# QFN-20_0_4mm.net
KiCad netlist of a schematic drawn in EAGLE
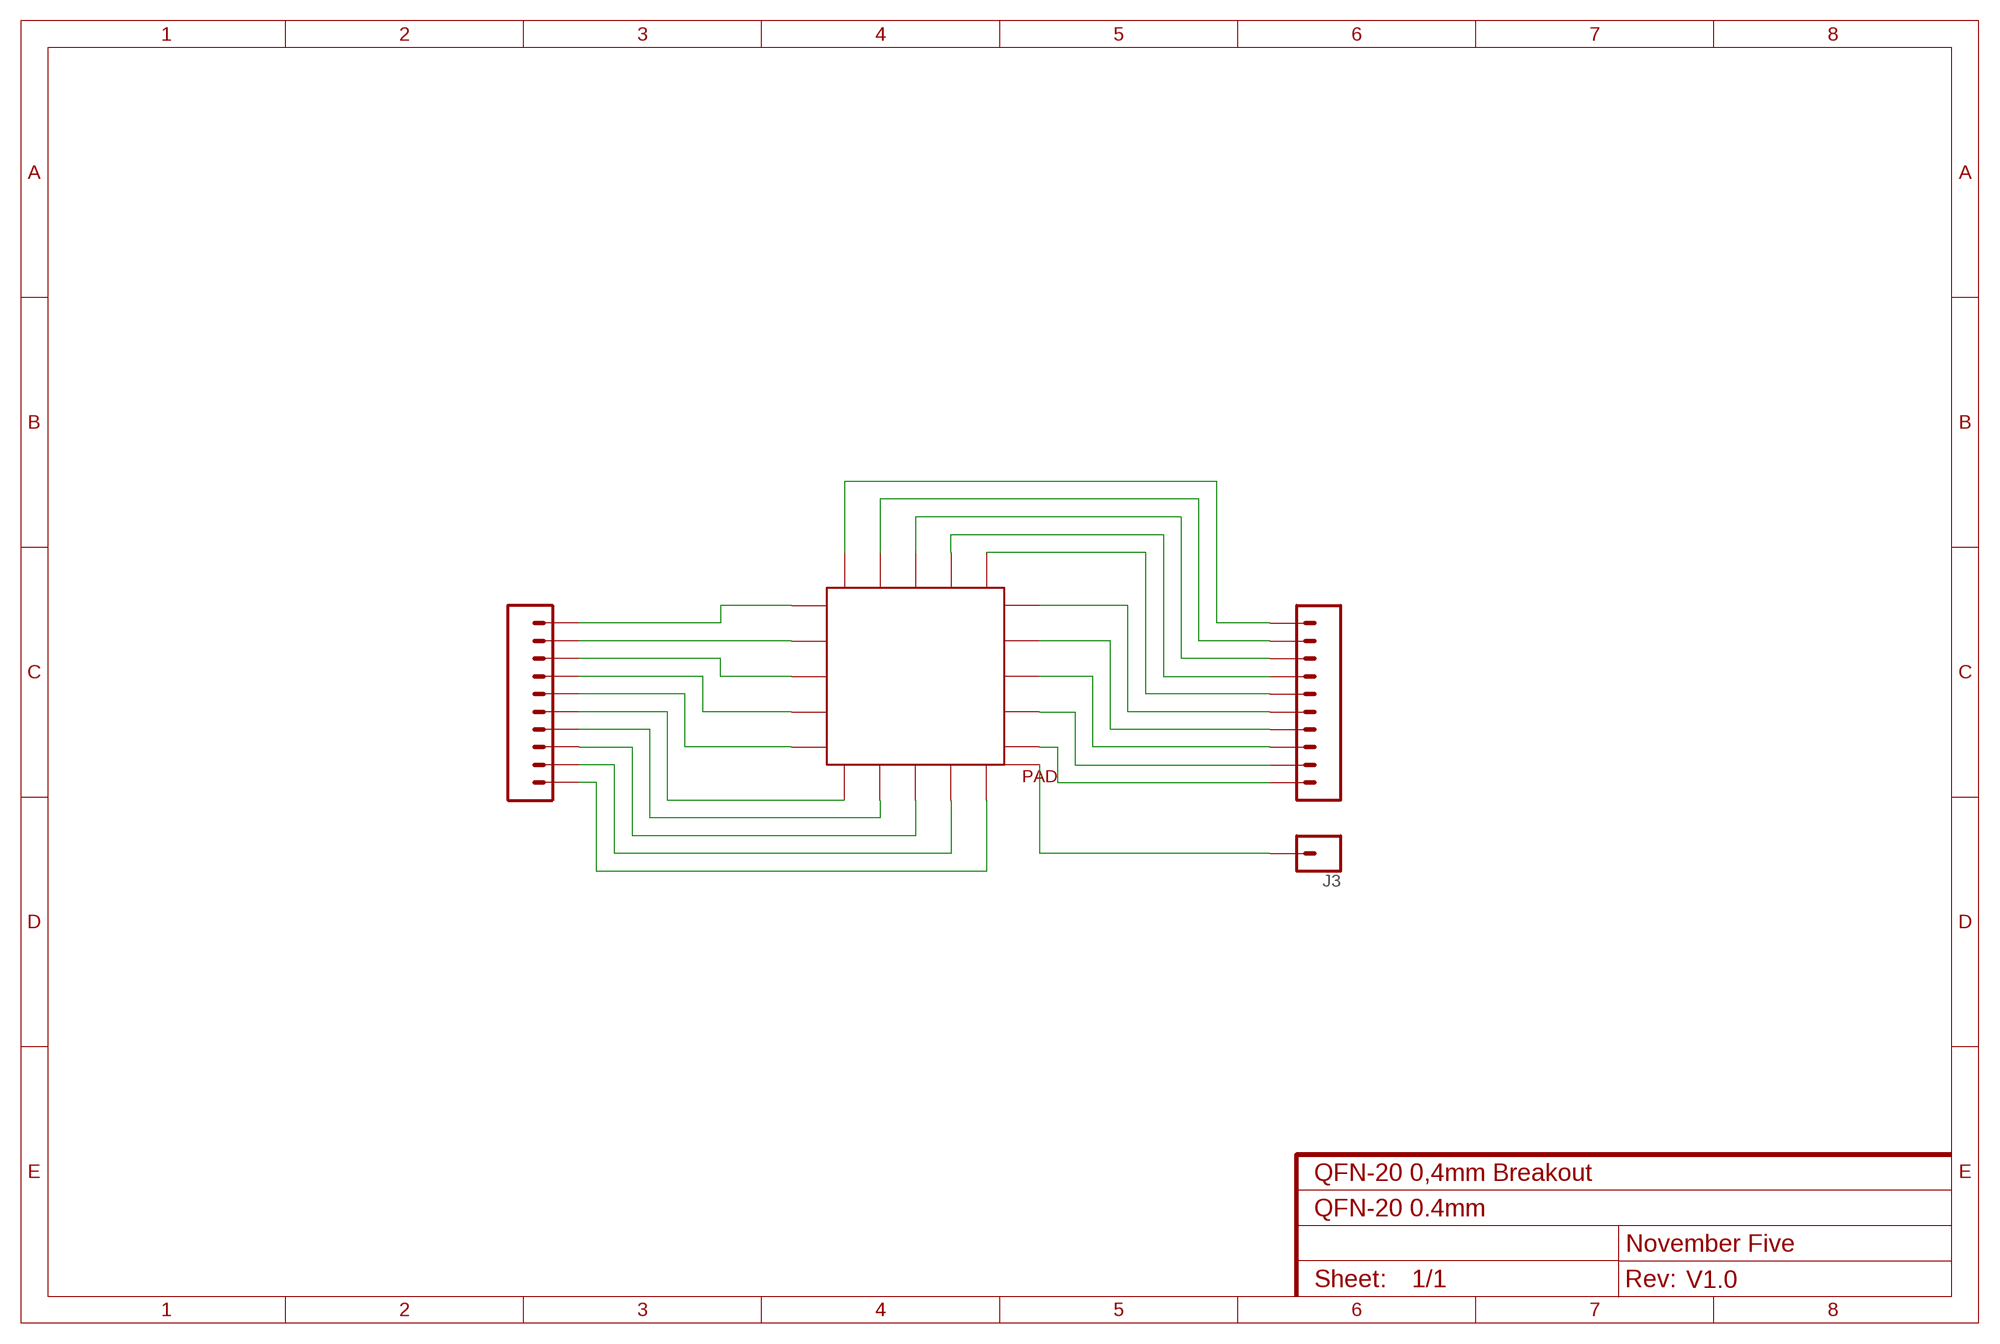
[diagram p0: schematic, sheet 1]

(export (version "E")
  (design (tool "Eeschema 10.0.6"))
  (components
    (comp (ref "GND")
      (value "QFN-20_0,4MM")
      (footprint "eagle-import:QFN20_0,4MM")
      (libsource (lib "eagle-import") (part "QFN-20_0,4MM"))
    )
    (comp (ref "J1")
      (value "CONN_10\"")
      (footprint "eagle-import:1X10")
      (libsource (lib "eagle-import") (part "CONN_10{dblquote}"))
    )
    (comp (ref "J2")
      (value "CONN_10\"")
      (footprint "eagle-import:1X10")
      (libsource (lib "eagle-import") (part "CONN_10{dblquote}"))
    )
    (comp (ref "J3")
      (value "CONN_01")
      (footprint "eagle-import:1X01")
      (libsource (lib "eagle-import") (part "CONN_01"))
    )
  )
  (nets
    (net (code "1") (name "Net-(GND-PAD)") (class "Default")
      (node (ref "GND") (pin "0") (pinfunction "PAD_0") (pintype "power_in"))
      (node (ref "J3") (pin "1") (pinfunction "1_1") (pintype "passive"))
    )
    (net (code "2") (name "Net-(GND-PIN1)") (class "Default")
      (node (ref "GND") (pin "1") (pinfunction "PIN1_1") (pintype "bidirectional"))
      (node (ref "J1") (pin "1") (pinfunction "1_1") (pintype "passive"))
    )
    (net (code "3") (name "Net-(GND-PIN2)") (class "Default")
      (node (ref "GND") (pin "2") (pinfunction "PIN2_2") (pintype "bidirectional"))
      (node (ref "J1") (pin "2") (pinfunction "2_2") (pintype "passive"))
    )
    (net (code "4") (name "Net-(GND-PIN3)") (class "Default")
      (node (ref "GND") (pin "3") (pinfunction "PIN3_3") (pintype "bidirectional"))
      (node (ref "J1") (pin "3") (pinfunction "3_3") (pintype "passive"))
    )
    (net (code "5") (name "Net-(GND-PIN4)") (class "Default")
      (node (ref "GND") (pin "4") (pinfunction "PIN4_4") (pintype "bidirectional"))
      (node (ref "J1") (pin "4") (pinfunction "4_4") (pintype "passive"))
    )
    (net (code "6") (name "Net-(GND-PIN5)") (class "Default")
      (node (ref "GND") (pin "5") (pinfunction "PIN5_5") (pintype "bidirectional"))
      (node (ref "J1") (pin "5") (pinfunction "5_5") (pintype "passive"))
    )
    (net (code "7") (name "Net-(GND-PIN6)") (class "Default")
      (node (ref "GND") (pin "6") (pinfunction "PIN6_6") (pintype "bidirectional"))
      (node (ref "J1") (pin "6") (pinfunction "6_6") (pintype "passive"))
    )
    (net (code "8") (name "Net-(GND-PIN7)") (class "Default")
      (node (ref "GND") (pin "7") (pinfunction "PIN7_7") (pintype "bidirectional"))
      (node (ref "J1") (pin "7") (pinfunction "7_7") (pintype "passive"))
    )
    (net (code "9") (name "Net-(GND-PIN8)") (class "Default")
      (node (ref "GND") (pin "8") (pinfunction "PIN8_8") (pintype "bidirectional"))
      (node (ref "J1") (pin "8") (pinfunction "8_8") (pintype "passive"))
    )
    (net (code "10") (name "Net-(GND-PIN9)") (class "Default")
      (node (ref "GND") (pin "9") (pinfunction "PIN9_9") (pintype "bidirectional"))
      (node (ref "J1") (pin "9") (pinfunction "9_9") (pintype "passive"))
    )
    (net (code "11") (name "Net-(GND-PIN10)") (class "Default")
      (node (ref "GND") (pin "10") (pinfunction "PIN10_10") (pintype "bidirectional"))
      (node (ref "J1") (pin "10") (pinfunction "10_10") (pintype "passive"))
    )
    (net (code "12") (name "Net-(GND-PIN11)") (class "Default")
      (node (ref "GND") (pin "11") (pinfunction "PIN11_11") (pintype "bidirectional"))
      (node (ref "J2") (pin "10") (pinfunction "10_10") (pintype "passive"))
    )
    (net (code "13") (name "Net-(GND-PIN12)") (class "Default")
      (node (ref "GND") (pin "12") (pinfunction "PIN12_12") (pintype "bidirectional"))
      (node (ref "J2") (pin "9") (pinfunction "9_9") (pintype "passive"))
    )
    (net (code "14") (name "Net-(GND-PIN13)") (class "Default")
      (node (ref "GND") (pin "13") (pinfunction "PIN13_13") (pintype "bidirectional"))
      (node (ref "J2") (pin "8") (pinfunction "8_8") (pintype "passive"))
    )
    (net (code "15") (name "Net-(GND-PIN14)") (class "Default")
      (node (ref "GND") (pin "14") (pinfunction "PIN14_14") (pintype "bidirectional"))
      (node (ref "J2") (pin "7") (pinfunction "7_7") (pintype "passive"))
    )
    (net (code "16") (name "Net-(GND-PIN15)") (class "Default")
      (node (ref "GND") (pin "15") (pinfunction "PIN15_15") (pintype "bidirectional"))
      (node (ref "J2") (pin "6") (pinfunction "6_6") (pintype "passive"))
    )
    (net (code "17") (name "Net-(GND-PIN16)") (class "Default")
      (node (ref "GND") (pin "16") (pinfunction "PIN16_16") (pintype "bidirectional"))
      (node (ref "J2") (pin "5") (pinfunction "5_5") (pintype "passive"))
    )
    (net (code "18") (name "Net-(GND-PIN17)") (class "Default")
      (node (ref "GND") (pin "17") (pinfunction "PIN17_17") (pintype "bidirectional"))
      (node (ref "J2") (pin "4") (pinfunction "4_4") (pintype "passive"))
    )
    (net (code "19") (name "Net-(GND-PIN18)") (class "Default")
      (node (ref "GND") (pin "18") (pinfunction "PIN18_18") (pintype "bidirectional"))
      (node (ref "J2") (pin "3") (pinfunction "3_3") (pintype "passive"))
    )
    (net (code "20") (name "Net-(GND-PIN19)") (class "Default")
      (node (ref "GND") (pin "19") (pinfunction "PIN19_19") (pintype "bidirectional"))
      (node (ref "J2") (pin "2") (pinfunction "2_2") (pintype "passive"))
    )
    (net (code "21") (name "Net-(GND-PIN20)") (class "Default")
      (node (ref "GND") (pin "20") (pinfunction "PIN20_20") (pintype "bidirectional"))
      (node (ref "J2") (pin "1") (pinfunction "1_1") (pintype "passive"))
    )
  )
)
